# Cabinet_System_Bmduino.net
KiCad netlist of a schematic drawn in Altium Designer
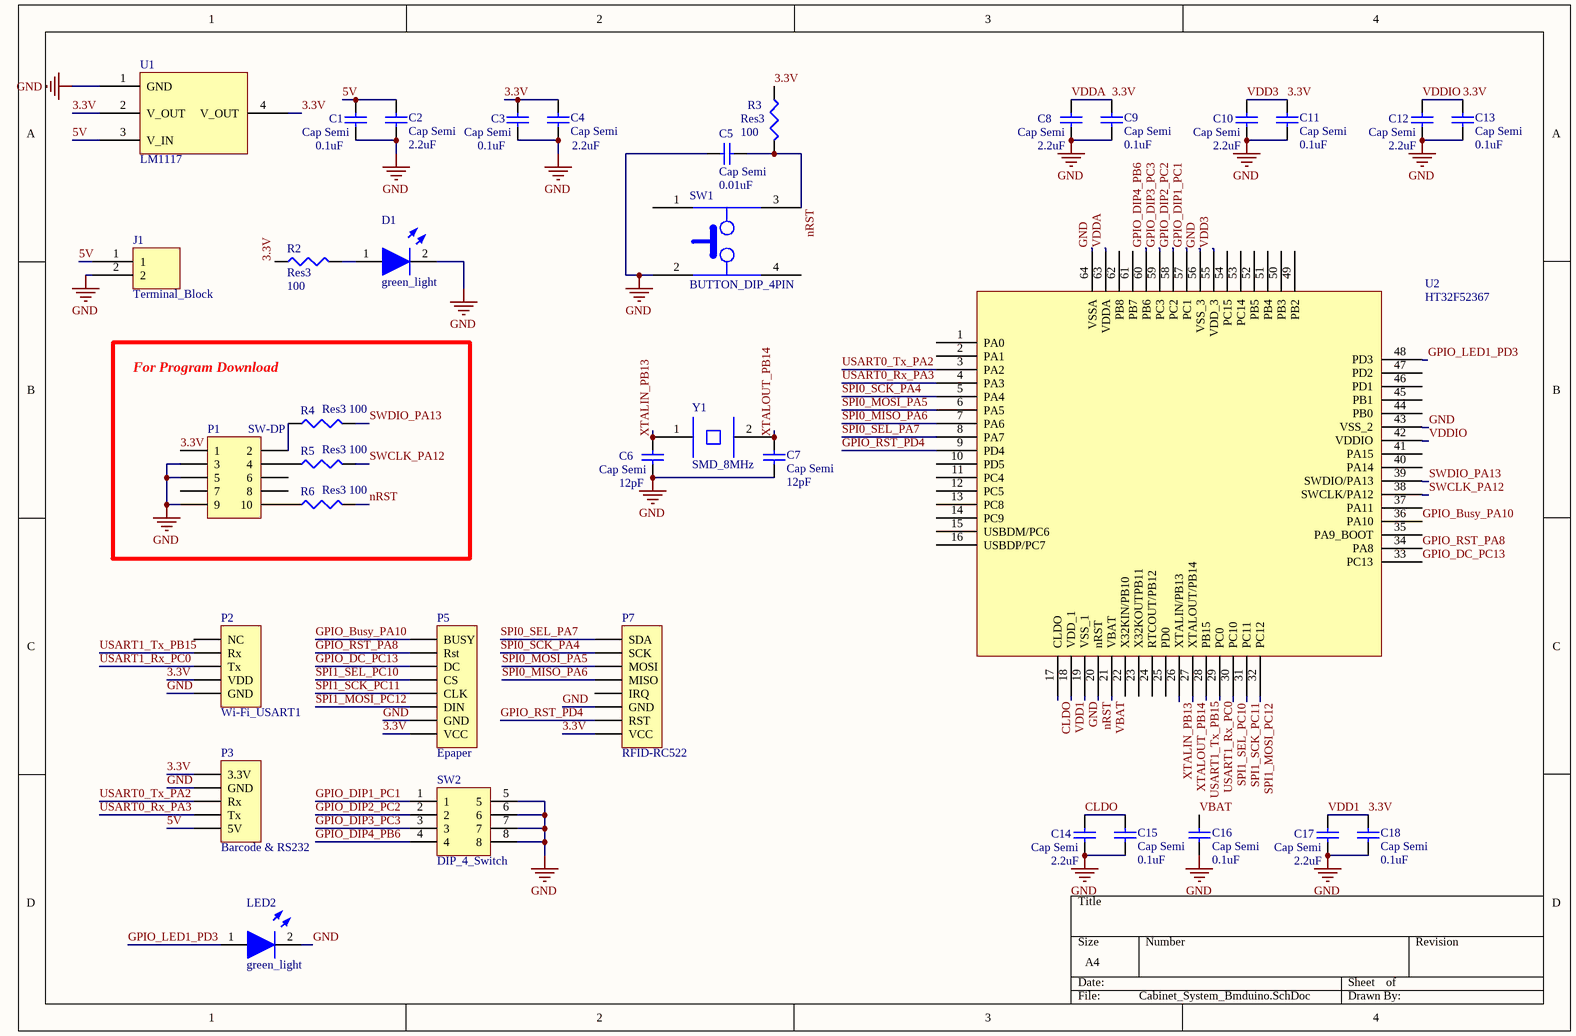
[diagram p0: Cabinet_System_Bmduino.SchDoc]

(export (version "E")
  (design (tool "Eeschema 10.0.6"))
  (components
    (comp (ref "C1")
      (value "Cap Semi")
      (footprint "1608[0603]")
      (description "Capacitor (Semiconductor SIM Model)")
      (fields (field (name "ALTIUM_VALUE") "0.1uF") (field (name "PUBLISHER") "Altium Limited"))
      (libsource (lib "Miscellaneous Devices") (part "Cap Semi"))
    )
    (comp (ref "C2")
      (value "Cap Semi")
      (footprint "1608[0603]")
      (description "Capacitor (Semiconductor SIM Model)")
      (fields (field (name "ALTIUM_VALUE") "2.2uF") (field (name "PUBLISHER") "Altium Limited"))
      (libsource (lib "Miscellaneous Devices") (part "Cap Semi"))
    )
    (comp (ref "C3")
      (value "Cap Semi")
      (footprint "1608[0603]")
      (description "Capacitor (Semiconductor SIM Model)")
      (fields (field (name "ALTIUM_VALUE") "0.1uF") (field (name "PUBLISHER") "Altium Limited"))
      (libsource (lib "Miscellaneous Devices") (part "Cap Semi"))
    )
    (comp (ref "C4")
      (value "Cap Semi")
      (footprint "1608[0603]")
      (description "Capacitor (Semiconductor SIM Model)")
      (fields (field (name "ALTIUM_VALUE") "2.2uF") (field (name "PUBLISHER") "Altium Limited"))
      (libsource (lib "Miscellaneous Devices") (part "Cap Semi"))
    )
    (comp (ref "C5")
      (value "Cap Semi")
      (footprint "1608[0603]")
      (description "Capacitor (Semiconductor SIM Model)")
      (fields (field (name "ALTIUM_VALUE") "0.01uF") (field (name "PUBLISHER") "Altium Limited"))
      (libsource (lib "Miscellaneous Devices") (part "Cap Semi"))
    )
    (comp (ref "C6")
      (value "Cap Semi")
      (footprint "1608[0603]")
      (description "Capacitor (Semiconductor SIM Model)")
      (fields (field (name "ALTIUM_VALUE") "12pF") (field (name "PUBLISHER") "Altium Limited"))
      (libsource (lib "Miscellaneous Devices") (part "Cap Semi"))
    )
    (comp (ref "C7")
      (value "Cap Semi")
      (footprint "1608[0603]")
      (description "Capacitor (Semiconductor SIM Model)")
      (fields (field (name "ALTIUM_VALUE") "12pF") (field (name "PUBLISHER") "Altium Limited"))
      (libsource (lib "Miscellaneous Devices") (part "Cap Semi"))
    )
    (comp (ref "C8")
      (value "Cap Semi")
      (footprint "1608[0603]")
      (description "Capacitor (Semiconductor SIM Model)")
      (fields (field (name "ALTIUM_VALUE") "2.2uF") (field (name "PUBLISHER") "Altium Limited"))
      (libsource (lib "Miscellaneous Devices") (part "Cap Semi"))
    )
    (comp (ref "C9")
      (value "Cap Semi")
      (footprint "1608[0603]")
      (description "Capacitor (Semiconductor SIM Model)")
      (fields (field (name "ALTIUM_VALUE") "0.1uF") (field (name "PUBLISHER") "Altium Limited"))
      (libsource (lib "Miscellaneous Devices") (part "Cap Semi"))
    )
    (comp (ref "C10")
      (value "Cap Semi")
      (footprint "1608[0603]")
      (description "Capacitor (Semiconductor SIM Model)")
      (fields (field (name "ALTIUM_VALUE") "2.2uF") (field (name "PUBLISHER") "Altium Limited"))
      (libsource (lib "Miscellaneous Devices") (part "Cap Semi"))
    )
    (comp (ref "C11")
      (value "Cap Semi")
      (footprint "1608[0603]")
      (description "Capacitor (Semiconductor SIM Model)")
      (fields (field (name "ALTIUM_VALUE") "0.1uF") (field (name "PUBLISHER") "Altium Limited"))
      (libsource (lib "Miscellaneous Devices") (part "Cap Semi"))
    )
    (comp (ref "C12")
      (value "Cap Semi")
      (footprint "1608[0603]")
      (description "Capacitor (Semiconductor SIM Model)")
      (fields (field (name "ALTIUM_VALUE") "2.2uF") (field (name "PUBLISHER") "Altium Limited"))
      (libsource (lib "Miscellaneous Devices") (part "Cap Semi"))
    )
    (comp (ref "C13")
      (value "Cap Semi")
      (footprint "1608[0603]")
      (description "Capacitor (Semiconductor SIM Model)")
      (fields (field (name "ALTIUM_VALUE") "0.1uF") (field (name "PUBLISHER") "Altium Limited"))
      (libsource (lib "Miscellaneous Devices") (part "Cap Semi"))
    )
    (comp (ref "C14")
      (value "Cap Semi")
      (footprint "1608[0603]")
      (description "Capacitor (Semiconductor SIM Model)")
      (fields (field (name "ALTIUM_VALUE") "2.2uF") (field (name "PUBLISHER") "Altium Limited"))
      (libsource (lib "Miscellaneous Devices") (part "Cap Semi"))
    )
    (comp (ref "C15")
      (value "Cap Semi")
      (footprint "1608[0603]")
      (description "Capacitor (Semiconductor SIM Model)")
      (fields (field (name "ALTIUM_VALUE") "0.1uF") (field (name "PUBLISHER") "Altium Limited"))
      (libsource (lib "Miscellaneous Devices") (part "Cap Semi"))
    )
    (comp (ref "C16")
      (value "Cap Semi")
      (footprint "1608[0603]")
      (description "Capacitor (Semiconductor SIM Model)")
      (fields (field (name "ALTIUM_VALUE") "0.1uF") (field (name "PUBLISHER") "Altium Limited"))
      (libsource (lib "Miscellaneous Devices") (part "Cap Semi"))
    )
    (comp (ref "C17")
      (value "Cap Semi")
      (footprint "1608[0603]")
      (description "Capacitor (Semiconductor SIM Model)")
      (fields (field (name "ALTIUM_VALUE") "2.2uF") (field (name "PUBLISHER") "Altium Limited"))
      (libsource (lib "Miscellaneous Devices") (part "Cap Semi"))
    )
    (comp (ref "C18")
      (value "Cap Semi")
      (footprint "1608[0603]")
      (description "Capacitor (Semiconductor SIM Model)")
      (fields (field (name "ALTIUM_VALUE") "0.1uF") (field (name "PUBLISHER") "Altium Limited"))
      (libsource (lib "Miscellaneous Devices") (part "Cap Semi"))
    )
    (comp (ref "D1")
      (value "green_light")
      (footprint "LED_Green")
      (libsource (lib "Lab_share") (part "LED_Green"))
    )
    (comp (ref "J1")
      (value "Terminal_Block")
      (footprint "terminal block")
      (libsource (lib "Lab_share") (part "Terminal Block"))
    )
    (comp (ref "LED2")
      (value "green_light")
      (footprint "LED_Green")
      (libsource (lib "Lab_share") (part "LED_Green"))
    )
    (comp (ref "P1")
      (value "SW-DP")
      (footprint "HDR2X5")
      (description "Header, 5-Pin, Dual row")
      (fields (field (name "PUBLISHER") "Altium Limited"))
      (libsource (lib "Miscellaneous Connectors") (part "Header 5X2"))
    )
    (comp (ref "P2")
      (value "Wi-Fi_USART1")
      (footprint "HDR1X5")
      (description "Header, 5-Pin")
      (fields (field (name "PUBLISHER") "Altium Limited"))
      (libsource (lib "Miscellaneous Connectors") (part "Header 5"))
    )
    (comp (ref "P3")
      (value "Barcode & RS232")
      (footprint "HDR1X5")
      (description "Header, 5-Pin")
      (fields (field (name "PUBLISHER") "Altium Limited"))
      (libsource (lib "Miscellaneous Connectors") (part "Header 5"))
    )
    (comp (ref "P5")
      (value "Epaper")
      (footprint "HDR1X8")
      (description "Header, 8-Pin")
      (fields (field (name "PUBLISHER") "Altium Limited"))
      (libsource (lib "Miscellaneous Connectors") (part "Header 8"))
    )
    (comp (ref "P7")
      (value "RFID-RC522")
      (footprint "HDR1X8")
      (description "Header, 8-Pin")
      (fields (field (name "PUBLISHER") "Altium Limited"))
      (libsource (lib "Miscellaneous Connectors") (part "Header 8"))
    )
    (comp (ref "R2")
      (value "Res3")
      (footprint "J1-0603")
      (description "Resistor")
      (fields (field (name "ALTIUM_VALUE") "100") (field (name "PUBLISHER") "Altium Limited"))
      (libsource (lib "Miscellaneous Devices") (part "Res3"))
    )
    (comp (ref "R3")
      (value "Res3")
      (footprint "J1-0603")
      (description "Resistor")
      (fields (field (name "ALTIUM_VALUE") "100") (field (name "PUBLISHER") "Altium Limited"))
      (libsource (lib "Miscellaneous Devices") (part "Res3"))
    )
    (comp (ref "R4")
      (value "Res3")
      (footprint "J1-0603")
      (description "Resistor")
      (fields (field (name "ALTIUM_VALUE") "100") (field (name "PUBLISHER") "Altium Limited"))
      (libsource (lib "Miscellaneous Devices") (part "Res3"))
    )
    (comp (ref "R5")
      (value "Res3")
      (footprint "J1-0603")
      (description "Resistor")
      (fields (field (name "ALTIUM_VALUE") "100") (field (name "PUBLISHER") "Altium Limited"))
      (libsource (lib "Miscellaneous Devices") (part "Res3"))
    )
    (comp (ref "R6")
      (value "Res3")
      (footprint "J1-0603")
      (description "Resistor")
      (fields (field (name "ALTIUM_VALUE") "100") (field (name "PUBLISHER") "Altium Limited"))
      (libsource (lib "Miscellaneous Devices") (part "Res3"))
    )
    (comp (ref "SW1")
      (value "BUTTON_DIP_4PIN")
      (footprint "Push_Button")
      (libsource (lib "Lab_share") (part "Push_Button"))
    )
    (comp (ref "SW2")
      (value "DIP_4_Switch")
      (footprint "Switch_4")
      (libsource (lib "Lab_share") (part "Switch_4"))
    )
    (comp (ref "U1")
      (value "LM1117")
      (footprint "LM1117 - duplicate")
      (libsource (lib "Lab_share") (part "LM1117"))
    )
    (comp (ref "U2")
      (value "HT32F52367")
      (footprint "HT32H52367")
      (libsource (lib "Lab_share") (part "HT32F52367"))
    )
    (comp (ref "Y1")
      (value "SMD_8MHz")
      (footprint "Quartz-Crystal-8MHz")
      (libsource (lib "Lab_share") (part "Quartz_Crystal_8MHz"))
    )
  )
  (nets
    (net (code "1") (name "/3.3V") (class "Default")
      (node (ref "C10") (pin "1") (pinfunction "1_1") (pintype "passive"))
      (node (ref "C11") (pin "2") (pinfunction "2_2") (pintype "passive"))
      (node (ref "C12") (pin "1") (pinfunction "1_1") (pintype "passive"))
      (node (ref "C13") (pin "2") (pinfunction "2_2") (pintype "passive"))
      (node (ref "C17") (pin "1") (pinfunction "1_1") (pintype "passive"))
      (node (ref "C18") (pin "2") (pinfunction "2_2") (pintype "passive"))
      (node (ref "C3") (pin "2") (pinfunction "2_2") (pintype "passive"))
      (node (ref "C4") (pin "2") (pinfunction "2_2") (pintype "passive"))
      (node (ref "C8") (pin "1") (pinfunction "1_1") (pintype "passive"))
      (node (ref "C9") (pin "2") (pinfunction "2_2") (pintype "passive"))
      (node (ref "P1") (pin "1") (pinfunction "1_1") (pintype "passive"))
      (node (ref "P2") (pin "4") (pinfunction "VDD_4") (pintype "passive"))
      (node (ref "P3") (pin "1") (pinfunction "NC_1") (pintype "passive"))
      (node (ref "P5") (pin "8") (pinfunction "VCC_8") (pintype "passive"))
      (node (ref "P7") (pin "8") (pinfunction "VCC_8") (pintype "passive"))
      (node (ref "R2") (pin "1") (pinfunction "1_1") (pintype "passive"))
      (node (ref "R3") (pin "1") (pinfunction "1_1") (pintype "passive"))
      (node (ref "U1") (pin "2") (pinfunction "V_OUT_2") (pintype "passive"))
      (node (ref "U1") (pin "4") (pinfunction "V_OUT_4") (pintype "passive"))
      (node (ref "U2") (pin "18") (pinfunction "VDD_1_18") (pintype "passive"))
      (node (ref "U2") (pin "42") (pinfunction "VDDIO_42") (pintype "passive"))
      (node (ref "U2") (pin "55") (pinfunction "VDD_3_55") (pintype "passive"))
      (node (ref "U2") (pin "63") (pinfunction "VDDA_63") (pintype "passive"))
    )
    (net (code "2") (name "/5V") (class "Default")
      (node (ref "C1") (pin "2") (pinfunction "2_2") (pintype "passive"))
      (node (ref "C2") (pin "2") (pinfunction "2_2") (pintype "passive"))
      (node (ref "J1") (pin "1") (pinfunction "1_1") (pintype "passive"))
      (node (ref "P3") (pin "5") (pinfunction "GND_5") (pintype "passive"))
      (node (ref "U1") (pin "3") (pinfunction "V_IN_3") (pintype "passive"))
    )
    (net (code "3") (name "/CLDO") (class "Default")
      (node (ref "C14") (pin "1") (pinfunction "1_1") (pintype "passive"))
      (node (ref "C15") (pin "2") (pinfunction "2_2") (pintype "passive"))
      (node (ref "U2") (pin "17") (pinfunction "CLDO_17") (pintype "passive"))
    )
    (net (code "4") (name "/GPIO_Busy_PA10") (class "Default")
      (node (ref "P5") (pin "1") (pinfunction "BUSY_1") (pintype "passive"))
      (node (ref "U2") (pin "36") (pinfunction "PA10_36") (pintype "passive"))
    )
    (net (code "5") (name "/GPIO_DC_PC13") (class "Default")
      (node (ref "P5") (pin "3") (pinfunction "DC_3") (pintype "passive"))
      (node (ref "U2") (pin "33") (pinfunction "PC13_33") (pintype "passive"))
    )
    (net (code "6") (name "/GPIO_DIP1_PC1") (class "Default")
      (node (ref "SW2") (pin "1") (pinfunction "1_1") (pintype "passive"))
      (node (ref "U2") (pin "57") (pinfunction "PC1_57") (pintype "passive"))
    )
    (net (code "7") (name "/GPIO_DIP2_PC2") (class "Default")
      (node (ref "SW2") (pin "2") (pinfunction "2_2") (pintype "passive"))
      (node (ref "U2") (pin "58") (pinfunction "PC2_58") (pintype "passive"))
    )
    (net (code "8") (name "/GPIO_DIP3_PC3") (class "Default")
      (node (ref "SW2") (pin "3") (pinfunction "3_3") (pintype "passive"))
      (node (ref "U2") (pin "59") (pinfunction "PC3_59") (pintype "passive"))
    )
    (net (code "9") (name "/GPIO_DIP4_PB6") (class "Default")
      (node (ref "SW2") (pin "4") (pinfunction "4_4") (pintype "passive"))
      (node (ref "U2") (pin "60") (pinfunction "PB6_60") (pintype "passive"))
    )
    (net (code "10") (name "/GPIO_LED1_PD3") (class "Default")
      (node (ref "LED2") (pin "1") (pintype "passive"))
      (node (ref "U2") (pin "48") (pinfunction "PD3_48") (pintype "passive"))
    )
    (net (code "11") (name "/GPIO_RST_PA8") (class "Default")
      (node (ref "P5") (pin "2") (pinfunction "Rst_2") (pintype "passive"))
      (node (ref "U2") (pin "34") (pinfunction "PA8_34") (pintype "passive"))
    )
    (net (code "12") (name "/GPIO_RST_PD4") (class "Default")
      (node (ref "P7") (pin "7") (pinfunction "GND_7") (pintype "passive"))
      (node (ref "U2") (pin "9") (pinfunction "PD4_9") (pintype "passive"))
    )
    (net (code "13") (name "/SPI0_MISO_PA6") (class "Default")
      (node (ref "P7") (pin "4") (pinfunction "CS_4") (pintype "passive"))
      (node (ref "U2") (pin "7") (pinfunction "PA6_7") (pintype "passive"))
    )
    (net (code "14") (name "/SPI0_MOSI_PA5") (class "Default")
      (node (ref "P7") (pin "3") (pinfunction "DC_3") (pintype "passive"))
      (node (ref "U2") (pin "6") (pinfunction "PA5_6") (pintype "passive"))
    )
    (net (code "15") (name "/SPI0_SCK_PA4") (class "Default")
      (node (ref "P7") (pin "2") (pinfunction "Rst_2") (pintype "passive"))
      (node (ref "U2") (pin "5") (pinfunction "PA4_5") (pintype "passive"))
    )
    (net (code "16") (name "/SPI0_SEL_PA7") (class "Default")
      (node (ref "P7") (pin "1") (pinfunction "BUSY_1") (pintype "passive"))
      (node (ref "U2") (pin "8") (pinfunction "PA7_8") (pintype "passive"))
    )
    (net (code "17") (name "/SPI1_MOSI_PC12") (class "Default")
      (node (ref "P5") (pin "6") (pinfunction "DIN_6") (pintype "passive"))
      (node (ref "U2") (pin "32") (pinfunction "PC12_32") (pintype "passive"))
    )
    (net (code "18") (name "/SPI1_SCK_PC11") (class "Default")
      (node (ref "P5") (pin "5") (pinfunction "CLK_5") (pintype "passive"))
      (node (ref "U2") (pin "31") (pinfunction "PC11_31") (pintype "passive"))
    )
    (net (code "19") (name "/SPI1_SEL_PC10") (class "Default")
      (node (ref "P5") (pin "4") (pinfunction "CS_4") (pintype "passive"))
      (node (ref "U2") (pin "30") (pinfunction "PC10_30") (pintype "passive"))
    )
    (net (code "20") (name "/SWCLK_PA12") (class "Default")
      (node (ref "R5") (pin "2") (pinfunction "2_2") (pintype "passive"))
      (node (ref "U2") (pin "38") (pinfunction "SWCLK/PA12_38") (pintype "passive"))
    )
    (net (code "21") (name "/SWDIO_PA13") (class "Default")
      (node (ref "R4") (pin "2") (pinfunction "2_2") (pintype "passive"))
      (node (ref "U2") (pin "39") (pinfunction "SWDIO/PA13_39") (pintype "passive"))
    )
    (net (code "22") (name "/USART0_Rx_PA3") (class "Default")
      (node (ref "P3") (pin "4") (pinfunction "VDD_4") (pintype "passive"))
      (node (ref "U2") (pin "4") (pinfunction "PA3_4") (pintype "passive"))
    )
    (net (code "23") (name "/USART0_Tx_PA2") (class "Default")
      (node (ref "P3") (pin "3") (pinfunction "Tx_3") (pintype "passive"))
      (node (ref "U2") (pin "3") (pinfunction "PA2_3") (pintype "passive"))
    )
    (net (code "24") (name "/USART1_Rx_PC0") (class "Default")
      (node (ref "P2") (pin "3") (pinfunction "Tx_3") (pintype "passive"))
      (node (ref "U2") (pin "29") (pinfunction "PC0_29") (pintype "passive"))
    )
    (net (code "25") (name "/USART1_Tx_PB15") (class "Default")
      (node (ref "P2") (pin "2") (pinfunction "Rx_2") (pintype "passive"))
      (node (ref "U2") (pin "28") (pinfunction "PB15_28") (pintype "passive"))
    )
    (net (code "26") (name "/VBAT") (class "Default")
      (node (ref "C16") (pin "2") (pinfunction "2_2") (pintype "passive"))
      (node (ref "U2") (pin "21") (pinfunction "VBAT_21") (pintype "passive"))
    )
    (net (code "27") (name "/XTALIN_PB13") (class "Default")
      (node (ref "C6") (pin "1") (pinfunction "1_1") (pintype "passive"))
      (node (ref "U2") (pin "26") (pinfunction "XTALIN/PB13_26") (pintype "passive"))
      (node (ref "Y1") (pin "1") (pintype "passive"))
    )
    (net (code "28") (name "/XTALOUT_PB14") (class "Default")
      (node (ref "C7") (pin "2") (pinfunction "2_2") (pintype "passive"))
      (node (ref "U2") (pin "27") (pinfunction "XTALOUT/PB14_27") (pintype "passive"))
      (node (ref "Y1") (pin "2") (pintype "passive"))
    )
    (net (code "29") (name "/nRST") (class "Default")
      (node (ref "C5") (pin "1") (pinfunction "1_1") (pintype "passive"))
      (node (ref "R3") (pin "2") (pinfunction "2_2") (pintype "passive"))
      (node (ref "R6") (pin "2") (pinfunction "2_2") (pintype "passive"))
      (node (ref "SW1") (pin "3") (pintype "passive"))
      (node (ref "U2") (pin "20") (pinfunction "nRST_20") (pintype "passive"))
    )
    (net (code "30") (name "GND") (class "Default")
      (node (ref "C1") (pin "1") (pinfunction "1_1") (pintype "passive"))
      (node (ref "C10") (pin "2") (pinfunction "2_2") (pintype "passive"))
      (node (ref "C11") (pin "1") (pinfunction "1_1") (pintype "passive"))
      (node (ref "C12") (pin "2") (pinfunction "2_2") (pintype "passive"))
      (node (ref "C13") (pin "1") (pinfunction "1_1") (pintype "passive"))
      (node (ref "C14") (pin "2") (pinfunction "2_2") (pintype "passive"))
      (node (ref "C15") (pin "1") (pinfunction "1_1") (pintype "passive"))
      (node (ref "C16") (pin "1") (pinfunction "1_1") (pintype "passive"))
      (node (ref "C17") (pin "2") (pinfunction "2_2") (pintype "passive"))
      (node (ref "C18") (pin "1") (pinfunction "1_1") (pintype "passive"))
      (node (ref "C2") (pin "1") (pinfunction "1_1") (pintype "passive"))
      (node (ref "C3") (pin "1") (pinfunction "1_1") (pintype "passive"))
      (node (ref "C4") (pin "1") (pinfunction "1_1") (pintype "passive"))
      (node (ref "C5") (pin "2") (pinfunction "2_2") (pintype "passive"))
      (node (ref "C6") (pin "2") (pinfunction "2_2") (pintype "passive"))
      (node (ref "C7") (pin "1") (pinfunction "1_1") (pintype "passive"))
      (node (ref "C8") (pin "2") (pinfunction "2_2") (pintype "passive"))
      (node (ref "C9") (pin "1") (pinfunction "1_1") (pintype "passive"))
      (node (ref "D1") (pin "2") (pintype "passive"))
      (node (ref "J1") (pin "2") (pinfunction "2_2") (pintype "passive"))
      (node (ref "LED2") (pin "2") (pintype "passive"))
      (node (ref "P1") (pin "3") (pinfunction "3_3") (pintype "passive"))
      (node (ref "P1") (pin "5") (pinfunction "5_5") (pintype "passive"))
      (node (ref "P1") (pin "9") (pinfunction "9_9") (pintype "passive"))
      (node (ref "P2") (pin "5") (pinfunction "GND_5") (pintype "passive"))
      (node (ref "P3") (pin "2") (pinfunction "Rx_2") (pintype "passive"))
      (node (ref "P5") (pin "7") (pinfunction "GND_7") (pintype "passive"))
      (node (ref "P7") (pin "6") (pinfunction "DIN_6") (pintype "passive"))
      (node (ref "SW1") (pin "2") (pintype "passive"))
      (node (ref "SW2") (pin "5") (pinfunction "5_5") (pintype "passive"))
      (node (ref "SW2") (pin "6") (pinfunction "6_6") (pintype "passive"))
      (node (ref "SW2") (pin "7") (pinfunction "7_7") (pintype "passive"))
      (node (ref "SW2") (pin "8") (pinfunction "8_8") (pintype "passive"))
      (node (ref "U1") (pin "1") (pinfunction "GND_1") (pintype "passive"))
      (node (ref "U2") (pin "19") (pinfunction "VSS_1_19") (pintype "passive"))
      (node (ref "U2") (pin "43") (pinfunction "VSS_2_43") (pintype "passive"))
      (node (ref "U2") (pin "56") (pinfunction "VSS_3_56") (pintype "passive"))
      (node (ref "U2") (pin "64") (pinfunction "VSSA_64") (pintype "passive"))
    )
    (net (code "31") (name "Net-(D1-Pad1)") (class "Default")
      (node (ref "D1") (pin "1") (pintype "passive"))
      (node (ref "R2") (pin "2") (pinfunction "2_2") (pintype "passive"))
    )
    (net (code "32") (name "Net-(P1-Pad2)") (class "Default")
      (node (ref "P1") (pin "2") (pinfunction "2_2") (pintype "passive"))
      (node (ref "R4") (pin "1") (pinfunction "1_1") (pintype "passive"))
    )
    (net (code "33") (name "Net-(P1-Pad4)") (class "Default")
      (node (ref "P1") (pin "4") (pinfunction "4_4") (pintype "passive"))
      (node (ref "R5") (pin "1") (pinfunction "1_1") (pintype "passive"))
    )
    (net (code "34") (name "Net-(P1-Pad10)") (class "Default")
      (node (ref "P1") (pin "10") (pinfunction "10_10") (pintype "passive"))
      (node (ref "R6") (pin "1") (pinfunction "1_1") (pintype "passive"))
    )
    (net (code "35") (name "unconnected-(P1-Pad6)") (class "Default")
      (node (ref "P1") (pin "6") (pinfunction "6_6") (pintype "passive"))
    )
    (net (code "36") (name "unconnected-(P1-Pad7)") (class "Default")
      (node (ref "P1") (pin "7") (pinfunction "7_7") (pintype "passive"))
    )
    (net (code "37") (name "unconnected-(P1-Pad8)") (class "Default")
      (node (ref "P1") (pin "8") (pinfunction "8_8") (pintype "passive"))
    )
    (net (code "38") (name "unconnected-(P2-NC-Pad1)") (class "Default")
      (node (ref "P2") (pin "1") (pinfunction "NC_1") (pintype "passive"))
    )
    (net (code "39") (name "unconnected-(P7-CLK-Pad5)") (class "Default")
      (node (ref "P7") (pin "5") (pinfunction "CLK_5") (pintype "passive"))
    )
    (net (code "40") (name "unconnected-(SW1-Pad1)") (class "Default")
      (node (ref "SW1") (pin "1") (pintype "passive"))
    )
    (net (code "41") (name "unconnected-(SW1-Pad4)") (class "Default")
      (node (ref "SW1") (pin "4") (pintype "passive"))
    )
    (net (code "42") (name "unconnected-(U2-PA0-Pad1)") (class "Default")
      (node (ref "U2") (pin "1") (pinfunction "PA0_1") (pintype "passive"))
    )
    (net (code "43") (name "unconnected-(U2-PA1-Pad2)") (class "Default")
      (node (ref "U2") (pin "2") (pinfunction "PA1_2") (pintype "passive"))
    )
    (net (code "44") (name "unconnected-(U2-PA9_BOOT-Pad35)") (class "Default")
      (node (ref "U2") (pin "35") (pinfunction "PA9_BOOT_35") (pintype "passive"))
    )
    (net (code "45") (name "unconnected-(U2-PA11-Pad37)") (class "Default")
      (node (ref "U2") (pin "37") (pinfunction "PA11_37") (pintype "passive"))
    )
    (net (code "46") (name "unconnected-(U2-PA14-Pad40)") (class "Default")
      (node (ref "U2") (pin "40") (pinfunction "PA14_40") (pintype "passive"))
    )
    (net (code "47") (name "unconnected-(U2-PA15-Pad41)") (class "Default")
      (node (ref "U2") (pin "41") (pinfunction "PA15_41") (pintype "passive"))
    )
    (net (code "48") (name "unconnected-(U2-PB0-Pad44)") (class "Default")
      (node (ref "U2") (pin "44") (pinfunction "PB0_44") (pintype "passive"))
    )
    (net (code "49") (name "unconnected-(U2-PB1-Pad45)") (class "Default")
      (node (ref "U2") (pin "45") (pinfunction "PB1_45") (pintype "passive"))
    )
    (net (code "50") (name "unconnected-(U2-PB2-Pad49)") (class "Default")
      (node (ref "U2") (pin "49") (pinfunction "PB2_49") (pintype "passive"))
    )
    (net (code "51") (name "unconnected-(U2-PB3-Pad50)") (class "Default")
      (node (ref "U2") (pin "50") (pinfunction "PB3_50") (pintype "passive"))
    )
    (net (code "52") (name "unconnected-(U2-PB4-Pad51)") (class "Default")
      (node (ref "U2") (pin "51") (pinfunction "PB4_51") (pintype "passive"))
    )
    (net (code "53") (name "unconnected-(U2-PB5-Pad52)") (class "Default")
      (node (ref "U2") (pin "52") (pinfunction "PB5_52") (pintype "passive"))
    )
    (net (code "54") (name "unconnected-(U2-PB7-Pad61)") (class "Default")
      (node (ref "U2") (pin "61") (pinfunction "PB7_61") (pintype "passive"))
    )
    (net (code "55") (name "unconnected-(U2-PB8-Pad62)") (class "Default")
      (node (ref "U2") (pin "62") (pinfunction "PB8_62") (pintype "passive"))
    )
    (net (code "56") (name "unconnected-(U2-PC4-Pad11)") (class "Default")
      (node (ref "U2") (pin "11") (pinfunction "PC4_11") (pintype "passive"))
    )
    (net (code "57") (name "unconnected-(U2-PC5-Pad12)") (class "Default")
      (node (ref "U2") (pin "12") (pinfunction "PC5_12") (pintype "passive"))
    )
    (net (code "58") (name "unconnected-(U2-PC8-Pad13)") (class "Default")
      (node (ref "U2") (pin "13") (pinfunction "PC8_13") (pintype "passive"))
    )
    (net (code "59") (name "unconnected-(U2-PC9-Pad14)") (class "Default")
      (node (ref "U2") (pin "14") (pinfunction "PC9_14") (pintype "passive"))
    )
    (net (code "60") (name "unconnected-(U2-PC14-Pad53)") (class "Default")
      (node (ref "U2") (pin "53") (pinfunction "PC14_53") (pintype "passive"))
    )
    (net (code "61") (name "unconnected-(U2-PC15-Pad54)") (class "Default")
      (node (ref "U2") (pin "54") (pinfunction "PC15_54") (pintype "passive"))
    )
    (net (code "62") (name "unconnected-(U2-PD0-Pad25)") (class "Default")
      (node (ref "U2") (pin "25") (pinfunction "PD0_25") (pintype "passive"))
    )
    (net (code "63") (name "unconnected-(U2-PD1-Pad46)") (class "Default")
      (node (ref "U2") (pin "46") (pinfunction "PD1_46") (pintype "passive"))
    )
    (net (code "64") (name "unconnected-(U2-PD2-Pad47)") (class "Default")
      (node (ref "U2") (pin "47") (pinfunction "PD2_47") (pintype "passive"))
    )
    (net (code "65") (name "unconnected-(U2-PD5-Pad10)") (class "Default")
      (node (ref "U2") (pin "10") (pinfunction "PD5_10") (pintype "passive"))
    )
    (net (code "66") (name "unconnected-(U2-RTCOUT{slash}PB12-Pad24)") (class "Default")
      (node (ref "U2") (pin "24") (pinfunction "RTCOUT/PB12_24") (pintype "passive"))
    )
    (net (code "67") (name "unconnected-(U2-USBDM{slash}PC6-Pad15)") (class "Default")
      (node (ref "U2") (pin "15") (pinfunction "USBDM/PC6_15") (pintype "passive"))
    )
    (net (code "68") (name "unconnected-(U2-USBDP{slash}PC7-Pad16)") (class "Default")
      (node (ref "U2") (pin "16") (pinfunction "USBDP/PC7_16") (pintype "passive"))
    )
    (net (code "69") (name "unconnected-(U2-X32KIN{slash}PB10-Pad22)") (class "Default")
      (node (ref "U2") (pin "22") (pinfunction "X32KIN/PB10_22") (pintype "passive"))
    )
    (net (code "70") (name "unconnected-(U2-X32KOUTPB11-Pad23)") (class "Default")
      (node (ref "U2") (pin "23") (pinfunction "X32KOUTPB11_23") (pintype "passive"))
    )
  )
)
